# KHR-1_Breakout_schm.net
KiCad netlist of a schematic drawn in EAGLE
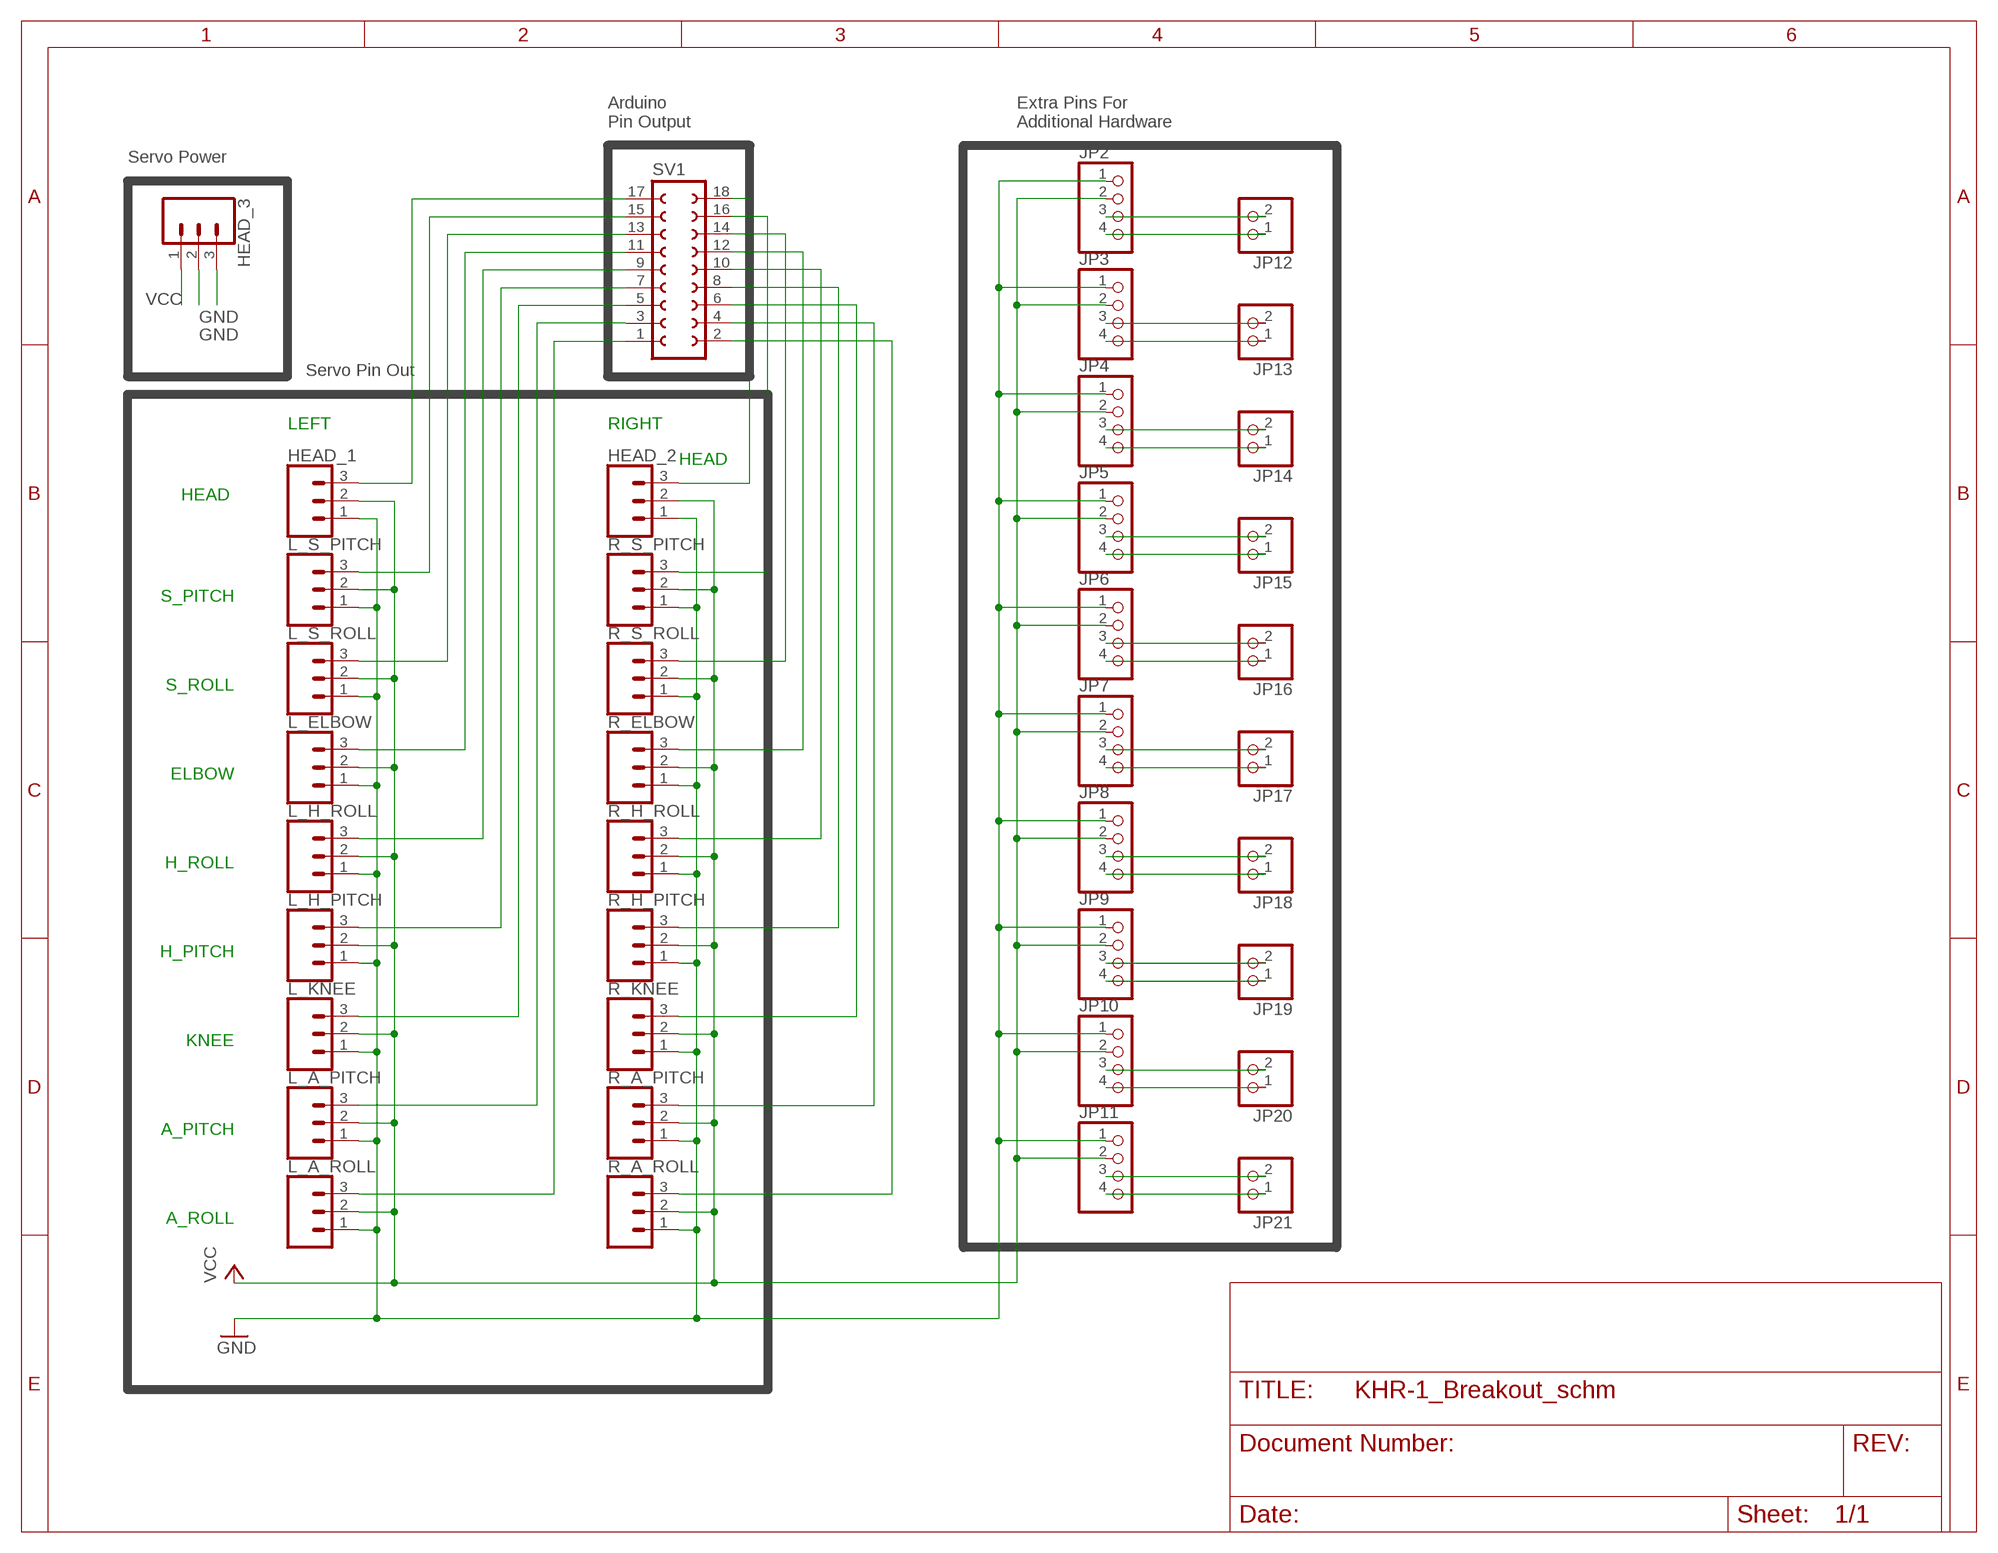
[diagram p0: schematic, sheet 1]

(export (version "E")
  (design (tool "Eeschema 10.0.6"))
  (components
    (comp (ref "HEAD_1")
      (value "CONN_03")
      (footprint "eagle-import:1X03")
      (libsource (lib "eagle-import") (part "CONN_03"))
    )
    (comp (ref "HEAD_2")
      (value "CONN_03")
      (footprint "eagle-import:1X03")
      (libsource (lib "eagle-import") (part "CONN_03"))
    )
    (comp (ref "HEAD_3")
      (value "CONN_03")
      (footprint "eagle-import:1X03")
      (libsource (lib "eagle-import") (part "CONN_03"))
    )
    (comp (ref "JP2")
      (value "PINHD-1X4")
      (footprint "eagle-import:1X04")
      (libsource (lib "eagle-import") (part "PINHD-1X4"))
    )
    (comp (ref "JP3")
      (value "PINHD-1X4")
      (footprint "eagle-import:1X04")
      (libsource (lib "eagle-import") (part "PINHD-1X4"))
    )
    (comp (ref "JP4")
      (value "PINHD-1X4")
      (footprint "eagle-import:1X04")
      (libsource (lib "eagle-import") (part "PINHD-1X4"))
    )
    (comp (ref "JP5")
      (value "PINHD-1X4")
      (footprint "eagle-import:1X04")
      (libsource (lib "eagle-import") (part "PINHD-1X4"))
    )
    (comp (ref "JP6")
      (value "PINHD-1X4")
      (footprint "eagle-import:1X04")
      (libsource (lib "eagle-import") (part "PINHD-1X4"))
    )
    (comp (ref "JP7")
      (value "PINHD-1X4")
      (footprint "eagle-import:1X04")
      (libsource (lib "eagle-import") (part "PINHD-1X4"))
    )
    (comp (ref "JP8")
      (value "PINHD-1X4")
      (footprint "eagle-import:1X04")
      (libsource (lib "eagle-import") (part "PINHD-1X4"))
    )
    (comp (ref "JP9")
      (value "PINHD-1X4")
      (footprint "eagle-import:1X04")
      (libsource (lib "eagle-import") (part "PINHD-1X4"))
    )
    (comp (ref "JP10")
      (value "PINHD-1X4")
      (footprint "eagle-import:1X04")
      (libsource (lib "eagle-import") (part "PINHD-1X4"))
    )
    (comp (ref "JP11")
      (value "PINHD-1X4")
      (footprint "eagle-import:1X04")
      (libsource (lib "eagle-import") (part "PINHD-1X4"))
    )
    (comp (ref "JP12")
      (value "PINHD-1X2")
      (footprint "eagle-import:1X02")
      (libsource (lib "eagle-import") (part "PINHD-1X2"))
    )
    (comp (ref "JP13")
      (value "PINHD-1X2")
      (footprint "eagle-import:1X02")
      (libsource (lib "eagle-import") (part "PINHD-1X2"))
    )
    (comp (ref "JP14")
      (value "PINHD-1X2")
      (footprint "eagle-import:1X02")
      (libsource (lib "eagle-import") (part "PINHD-1X2"))
    )
    (comp (ref "JP15")
      (value "PINHD-1X2")
      (footprint "eagle-import:1X02")
      (libsource (lib "eagle-import") (part "PINHD-1X2"))
    )
    (comp (ref "JP16")
      (value "PINHD-1X2")
      (footprint "eagle-import:1X02")
      (libsource (lib "eagle-import") (part "PINHD-1X2"))
    )
    (comp (ref "JP17")
      (value "PINHD-1X2")
      (footprint "eagle-import:1X02")
      (libsource (lib "eagle-import") (part "PINHD-1X2"))
    )
    (comp (ref "JP18")
      (value "PINHD-1X2")
      (footprint "eagle-import:1X02")
      (libsource (lib "eagle-import") (part "PINHD-1X2"))
    )
    (comp (ref "JP19")
      (value "PINHD-1X2")
      (footprint "eagle-import:1X02")
      (libsource (lib "eagle-import") (part "PINHD-1X2"))
    )
    (comp (ref "JP20")
      (value "PINHD-1X2")
      (footprint "eagle-import:1X02")
      (libsource (lib "eagle-import") (part "PINHD-1X2"))
    )
    (comp (ref "JP21")
      (value "PINHD-1X2")
      (footprint "eagle-import:1X02")
      (libsource (lib "eagle-import") (part "PINHD-1X2"))
    )
    (comp (ref "L_A_PITCH")
      (value "CONN_03")
      (footprint "eagle-import:1X03")
      (libsource (lib "eagle-import") (part "CONN_03"))
    )
    (comp (ref "L_A_ROLL")
      (value "CONN_03")
      (footprint "eagle-import:1X03")
      (libsource (lib "eagle-import") (part "CONN_03"))
    )
    (comp (ref "L_ELBOW")
      (value "CONN_03")
      (footprint "eagle-import:1X03")
      (libsource (lib "eagle-import") (part "CONN_03"))
    )
    (comp (ref "L_H_PITCH")
      (value "CONN_03")
      (footprint "eagle-import:1X03")
      (libsource (lib "eagle-import") (part "CONN_03"))
    )
    (comp (ref "L_H_ROLL")
      (value "CONN_03")
      (footprint "eagle-import:1X03")
      (libsource (lib "eagle-import") (part "CONN_03"))
    )
    (comp (ref "L_KNEE")
      (value "CONN_03")
      (footprint "eagle-import:1X03")
      (libsource (lib "eagle-import") (part "CONN_03"))
    )
    (comp (ref "L_S_PITCH")
      (value "CONN_03")
      (footprint "eagle-import:1X03")
      (libsource (lib "eagle-import") (part "CONN_03"))
    )
    (comp (ref "L_S_ROLL")
      (value "CONN_03")
      (footprint "eagle-import:1X03")
      (libsource (lib "eagle-import") (part "CONN_03"))
    )
    (comp (ref "R_A_PITCH")
      (value "CONN_03")
      (footprint "eagle-import:1X03")
      (libsource (lib "eagle-import") (part "CONN_03"))
    )
    (comp (ref "R_A_ROLL")
      (value "CONN_03")
      (footprint "eagle-import:1X03")
      (libsource (lib "eagle-import") (part "CONN_03"))
    )
    (comp (ref "R_ELBOW")
      (value "CONN_03")
      (footprint "eagle-import:1X03")
      (libsource (lib "eagle-import") (part "CONN_03"))
    )
    (comp (ref "R_H_PITCH")
      (value "CONN_03")
      (footprint "eagle-import:1X03")
      (libsource (lib "eagle-import") (part "CONN_03"))
    )
    (comp (ref "R_H_ROLL")
      (value "CONN_03")
      (footprint "eagle-import:1X03")
      (libsource (lib "eagle-import") (part "CONN_03"))
    )
    (comp (ref "R_KNEE")
      (value "CONN_03")
      (footprint "eagle-import:1X03")
      (libsource (lib "eagle-import") (part "CONN_03"))
    )
    (comp (ref "R_S_PITCH")
      (value "CONN_03")
      (footprint "eagle-import:1X03")
      (libsource (lib "eagle-import") (part "CONN_03"))
    )
    (comp (ref "R_S_ROLL")
      (value "CONN_03")
      (footprint "eagle-import:1X03")
      (libsource (lib "eagle-import") (part "CONN_03"))
    )
    (comp (ref "SV1")
      (value "FE09-2")
      (footprint "eagle-import:FE09-2")
      (libsource (lib "eagle-import") (part "FE09-2"))
    )
  )
  (nets
    (net (code "1") (name "GND") (class "Default")
      (node (ref "HEAD_1") (pin "1") (pinfunction "1_1") (pintype "passive"))
      (node (ref "HEAD_2") (pin "1") (pinfunction "1_1") (pintype "passive"))
      (node (ref "HEAD_3") (pin "2") (pinfunction "2_2") (pintype "passive"))
      (node (ref "HEAD_3") (pin "3") (pinfunction "3_3") (pintype "passive"))
      (node (ref "JP10") (pin "1") (pinfunction "1_1") (pintype "passive"))
      (node (ref "JP11") (pin "1") (pinfunction "1_1") (pintype "passive"))
      (node (ref "JP2") (pin "1") (pinfunction "1_1") (pintype "passive"))
      (node (ref "JP3") (pin "1") (pinfunction "1_1") (pintype "passive"))
      (node (ref "JP4") (pin "1") (pinfunction "1_1") (pintype "passive"))
      (node (ref "JP5") (pin "1") (pinfunction "1_1") (pintype "passive"))
      (node (ref "JP6") (pin "1") (pinfunction "1_1") (pintype "passive"))
      (node (ref "JP7") (pin "1") (pinfunction "1_1") (pintype "passive"))
      (node (ref "JP8") (pin "1") (pinfunction "1_1") (pintype "passive"))
      (node (ref "JP9") (pin "1") (pinfunction "1_1") (pintype "passive"))
      (node (ref "L_A_PITCH") (pin "1") (pinfunction "1_1") (pintype "passive"))
      (node (ref "L_A_ROLL") (pin "1") (pinfunction "1_1") (pintype "passive"))
      (node (ref "L_ELBOW") (pin "1") (pinfunction "1_1") (pintype "passive"))
      (node (ref "L_H_PITCH") (pin "1") (pinfunction "1_1") (pintype "passive"))
      (node (ref "L_H_ROLL") (pin "1") (pinfunction "1_1") (pintype "passive"))
      (node (ref "L_KNEE") (pin "1") (pinfunction "1_1") (pintype "passive"))
      (node (ref "L_S_PITCH") (pin "1") (pinfunction "1_1") (pintype "passive"))
      (node (ref "L_S_ROLL") (pin "1") (pinfunction "1_1") (pintype "passive"))
      (node (ref "R_A_PITCH") (pin "1") (pinfunction "1_1") (pintype "passive"))
      (node (ref "R_A_ROLL") (pin "1") (pinfunction "1_1") (pintype "passive"))
      (node (ref "R_ELBOW") (pin "1") (pinfunction "1_1") (pintype "passive"))
      (node (ref "R_H_PITCH") (pin "1") (pinfunction "1_1") (pintype "passive"))
      (node (ref "R_H_ROLL") (pin "1") (pinfunction "1_1") (pintype "passive"))
      (node (ref "R_KNEE") (pin "1") (pinfunction "1_1") (pintype "passive"))
      (node (ref "R_S_PITCH") (pin "1") (pinfunction "1_1") (pintype "passive"))
      (node (ref "R_S_ROLL") (pin "1") (pinfunction "1_1") (pintype "passive"))
    )
    (net (code "2") (name "Net-(HEAD_1-Pad3)") (class "Default")
      (node (ref "HEAD_1") (pin "3") (pinfunction "3_3") (pintype "passive"))
      (node (ref "SV1") (pin "17") (pinfunction "17_17") (pintype "passive"))
    )
    (net (code "3") (name "Net-(HEAD_2-Pad3)") (class "Default")
      (node (ref "HEAD_2") (pin "3") (pinfunction "3_3") (pintype "passive"))
      (node (ref "SV1") (pin "18") (pinfunction "18_18") (pintype "passive"))
    )
    (net (code "4") (name "Net-(JP10-Pad3)") (class "Default")
      (node (ref "JP10") (pin "3") (pinfunction "3_3") (pintype "passive"))
      (node (ref "JP20") (pin "2") (pinfunction "2_2") (pintype "passive"))
    )
    (net (code "5") (name "Net-(JP10-Pad4)") (class "Default")
      (node (ref "JP10") (pin "4") (pinfunction "4_4") (pintype "passive"))
      (node (ref "JP20") (pin "1") (pinfunction "1_1") (pintype "passive"))
    )
    (net (code "6") (name "Net-(JP11-Pad3)") (class "Default")
      (node (ref "JP11") (pin "3") (pinfunction "3_3") (pintype "passive"))
      (node (ref "JP21") (pin "2") (pinfunction "2_2") (pintype "passive"))
    )
    (net (code "7") (name "Net-(JP11-Pad4)") (class "Default")
      (node (ref "JP11") (pin "4") (pinfunction "4_4") (pintype "passive"))
      (node (ref "JP21") (pin "1") (pinfunction "1_1") (pintype "passive"))
    )
    (net (code "8") (name "Net-(JP12-Pad1)") (class "Default")
      (node (ref "JP12") (pin "1") (pinfunction "1_1") (pintype "passive"))
      (node (ref "JP2") (pin "4") (pinfunction "4_4") (pintype "passive"))
    )
    (net (code "9") (name "Net-(JP12-Pad2)") (class "Default")
      (node (ref "JP12") (pin "2") (pinfunction "2_2") (pintype "passive"))
      (node (ref "JP2") (pin "3") (pinfunction "3_3") (pintype "passive"))
    )
    (net (code "10") (name "Net-(JP13-Pad1)") (class "Default")
      (node (ref "JP13") (pin "1") (pinfunction "1_1") (pintype "passive"))
      (node (ref "JP3") (pin "4") (pinfunction "4_4") (pintype "passive"))
    )
    (net (code "11") (name "Net-(JP13-Pad2)") (class "Default")
      (node (ref "JP13") (pin "2") (pinfunction "2_2") (pintype "passive"))
      (node (ref "JP3") (pin "3") (pinfunction "3_3") (pintype "passive"))
    )
    (net (code "12") (name "Net-(JP14-Pad1)") (class "Default")
      (node (ref "JP14") (pin "1") (pinfunction "1_1") (pintype "passive"))
      (node (ref "JP4") (pin "4") (pinfunction "4_4") (pintype "passive"))
    )
    (net (code "13") (name "Net-(JP14-Pad2)") (class "Default")
      (node (ref "JP14") (pin "2") (pinfunction "2_2") (pintype "passive"))
      (node (ref "JP4") (pin "3") (pinfunction "3_3") (pintype "passive"))
    )
    (net (code "14") (name "Net-(JP15-Pad1)") (class "Default")
      (node (ref "JP15") (pin "1") (pinfunction "1_1") (pintype "passive"))
      (node (ref "JP5") (pin "4") (pinfunction "4_4") (pintype "passive"))
    )
    (net (code "15") (name "Net-(JP15-Pad2)") (class "Default")
      (node (ref "JP15") (pin "2") (pinfunction "2_2") (pintype "passive"))
      (node (ref "JP5") (pin "3") (pinfunction "3_3") (pintype "passive"))
    )
    (net (code "16") (name "Net-(JP16-Pad1)") (class "Default")
      (node (ref "JP16") (pin "1") (pinfunction "1_1") (pintype "passive"))
      (node (ref "JP6") (pin "4") (pinfunction "4_4") (pintype "passive"))
    )
    (net (code "17") (name "Net-(JP16-Pad2)") (class "Default")
      (node (ref "JP16") (pin "2") (pinfunction "2_2") (pintype "passive"))
      (node (ref "JP6") (pin "3") (pinfunction "3_3") (pintype "passive"))
    )
    (net (code "18") (name "Net-(JP17-Pad1)") (class "Default")
      (node (ref "JP17") (pin "1") (pinfunction "1_1") (pintype "passive"))
      (node (ref "JP7") (pin "4") (pinfunction "4_4") (pintype "passive"))
    )
    (net (code "19") (name "Net-(JP17-Pad2)") (class "Default")
      (node (ref "JP17") (pin "2") (pinfunction "2_2") (pintype "passive"))
      (node (ref "JP7") (pin "3") (pinfunction "3_3") (pintype "passive"))
    )
    (net (code "20") (name "Net-(JP18-Pad1)") (class "Default")
      (node (ref "JP18") (pin "1") (pinfunction "1_1") (pintype "passive"))
      (node (ref "JP8") (pin "4") (pinfunction "4_4") (pintype "passive"))
    )
    (net (code "21") (name "Net-(JP18-Pad2)") (class "Default")
      (node (ref "JP18") (pin "2") (pinfunction "2_2") (pintype "passive"))
      (node (ref "JP8") (pin "3") (pinfunction "3_3") (pintype "passive"))
    )
    (net (code "22") (name "Net-(JP19-Pad1)") (class "Default")
      (node (ref "JP19") (pin "1") (pinfunction "1_1") (pintype "passive"))
      (node (ref "JP9") (pin "4") (pinfunction "4_4") (pintype "passive"))
    )
    (net (code "23") (name "Net-(JP19-Pad2)") (class "Default")
      (node (ref "JP19") (pin "2") (pinfunction "2_2") (pintype "passive"))
      (node (ref "JP9") (pin "3") (pinfunction "3_3") (pintype "passive"))
    )
    (net (code "24") (name "Net-(L_A_PITCH-Pad3)") (class "Default")
      (node (ref "L_A_PITCH") (pin "3") (pinfunction "3_3") (pintype "passive"))
      (node (ref "SV1") (pin "3") (pinfunction "3_3") (pintype "passive"))
    )
    (net (code "25") (name "Net-(L_A_ROLL-Pad3)") (class "Default")
      (node (ref "L_A_ROLL") (pin "3") (pinfunction "3_3") (pintype "passive"))
      (node (ref "SV1") (pin "1") (pinfunction "1_1") (pintype "passive"))
    )
    (net (code "26") (name "Net-(L_ELBOW-Pad3)") (class "Default")
      (node (ref "L_ELBOW") (pin "3") (pinfunction "3_3") (pintype "passive"))
      (node (ref "SV1") (pin "11") (pinfunction "11_11") (pintype "passive"))
    )
    (net (code "27") (name "Net-(L_H_PITCH-Pad3)") (class "Default")
      (node (ref "L_H_PITCH") (pin "3") (pinfunction "3_3") (pintype "passive"))
      (node (ref "SV1") (pin "7") (pinfunction "7_7") (pintype "passive"))
    )
    (net (code "28") (name "Net-(L_H_ROLL-Pad3)") (class "Default")
      (node (ref "L_H_ROLL") (pin "3") (pinfunction "3_3") (pintype "passive"))
      (node (ref "SV1") (pin "9") (pinfunction "9_9") (pintype "passive"))
    )
    (net (code "29") (name "Net-(L_KNEE-Pad3)") (class "Default")
      (node (ref "L_KNEE") (pin "3") (pinfunction "3_3") (pintype "passive"))
      (node (ref "SV1") (pin "5") (pinfunction "5_5") (pintype "passive"))
    )
    (net (code "30") (name "Net-(L_S_PITCH-Pad3)") (class "Default")
      (node (ref "L_S_PITCH") (pin "3") (pinfunction "3_3") (pintype "passive"))
      (node (ref "SV1") (pin "15") (pinfunction "15_15") (pintype "passive"))
    )
    (net (code "31") (name "Net-(L_S_ROLL-Pad3)") (class "Default")
      (node (ref "L_S_ROLL") (pin "3") (pinfunction "3_3") (pintype "passive"))
      (node (ref "SV1") (pin "13") (pinfunction "13_13") (pintype "passive"))
    )
    (net (code "32") (name "Net-(R_A_PITCH-Pad3)") (class "Default")
      (node (ref "R_A_PITCH") (pin "3") (pinfunction "3_3") (pintype "passive"))
      (node (ref "SV1") (pin "4") (pinfunction "4_4") (pintype "passive"))
    )
    (net (code "33") (name "Net-(R_A_ROLL-Pad3)") (class "Default")
      (node (ref "R_A_ROLL") (pin "3") (pinfunction "3_3") (pintype "passive"))
      (node (ref "SV1") (pin "2") (pinfunction "2_2") (pintype "passive"))
    )
    (net (code "34") (name "Net-(R_ELBOW-Pad3)") (class "Default")
      (node (ref "R_ELBOW") (pin "3") (pinfunction "3_3") (pintype "passive"))
      (node (ref "SV1") (pin "12") (pinfunction "12_12") (pintype "passive"))
    )
    (net (code "35") (name "Net-(R_H_PITCH-Pad3)") (class "Default")
      (node (ref "R_H_PITCH") (pin "3") (pinfunction "3_3") (pintype "passive"))
      (node (ref "SV1") (pin "8") (pinfunction "8_8") (pintype "passive"))
    )
    (net (code "36") (name "Net-(R_H_ROLL-Pad3)") (class "Default")
      (node (ref "R_H_ROLL") (pin "3") (pinfunction "3_3") (pintype "passive"))
      (node (ref "SV1") (pin "10") (pinfunction "10_10") (pintype "passive"))
    )
    (net (code "37") (name "Net-(R_KNEE-Pad3)") (class "Default")
      (node (ref "R_KNEE") (pin "3") (pinfunction "3_3") (pintype "passive"))
      (node (ref "SV1") (pin "6") (pinfunction "6_6") (pintype "passive"))
    )
    (net (code "38") (name "Net-(R_S_PITCH-Pad3)") (class "Default")
      (node (ref "R_S_PITCH") (pin "3") (pinfunction "3_3") (pintype "passive"))
      (node (ref "SV1") (pin "16") (pinfunction "16_16") (pintype "passive"))
    )
    (net (code "39") (name "Net-(R_S_ROLL-Pad3)") (class "Default")
      (node (ref "R_S_ROLL") (pin "3") (pinfunction "3_3") (pintype "passive"))
      (node (ref "SV1") (pin "14") (pinfunction "14_14") (pintype "passive"))
    )
    (net (code "40") (name "VCC") (class "Default")
      (node (ref "HEAD_1") (pin "2") (pinfunction "2_2") (pintype "passive"))
      (node (ref "HEAD_2") (pin "2") (pinfunction "2_2") (pintype "passive"))
      (node (ref "HEAD_3") (pin "1") (pinfunction "1_1") (pintype "passive"))
      (node (ref "JP10") (pin "2") (pinfunction "2_2") (pintype "passive"))
      (node (ref "JP11") (pin "2") (pinfunction "2_2") (pintype "passive"))
      (node (ref "JP2") (pin "2") (pinfunction "2_2") (pintype "passive"))
      (node (ref "JP3") (pin "2") (pinfunction "2_2") (pintype "passive"))
      (node (ref "JP4") (pin "2") (pinfunction "2_2") (pintype "passive"))
      (node (ref "JP5") (pin "2") (pinfunction "2_2") (pintype "passive"))
      (node (ref "JP6") (pin "2") (pinfunction "2_2") (pintype "passive"))
      (node (ref "JP7") (pin "2") (pinfunction "2_2") (pintype "passive"))
      (node (ref "JP8") (pin "2") (pinfunction "2_2") (pintype "passive"))
      (node (ref "JP9") (pin "2") (pinfunction "2_2") (pintype "passive"))
      (node (ref "L_A_PITCH") (pin "2") (pinfunction "2_2") (pintype "passive"))
      (node (ref "L_A_ROLL") (pin "2") (pinfunction "2_2") (pintype "passive"))
      (node (ref "L_ELBOW") (pin "2") (pinfunction "2_2") (pintype "passive"))
      (node (ref "L_H_PITCH") (pin "2") (pinfunction "2_2") (pintype "passive"))
      (node (ref "L_H_ROLL") (pin "2") (pinfunction "2_2") (pintype "passive"))
      (node (ref "L_KNEE") (pin "2") (pinfunction "2_2") (pintype "passive"))
      (node (ref "L_S_PITCH") (pin "2") (pinfunction "2_2") (pintype "passive"))
      (node (ref "L_S_ROLL") (pin "2") (pinfunction "2_2") (pintype "passive"))
      (node (ref "R_A_PITCH") (pin "2") (pinfunction "2_2") (pintype "passive"))
      (node (ref "R_A_ROLL") (pin "2") (pinfunction "2_2") (pintype "passive"))
      (node (ref "R_ELBOW") (pin "2") (pinfunction "2_2") (pintype "passive"))
      (node (ref "R_H_PITCH") (pin "2") (pinfunction "2_2") (pintype "passive"))
      (node (ref "R_H_ROLL") (pin "2") (pinfunction "2_2") (pintype "passive"))
      (node (ref "R_KNEE") (pin "2") (pinfunction "2_2") (pintype "passive"))
      (node (ref "R_S_PITCH") (pin "2") (pinfunction "2_2") (pintype "passive"))
      (node (ref "R_S_ROLL") (pin "2") (pinfunction "2_2") (pintype "passive"))
    )
  )
)
